# OBD_Board_Ver1.net
KiCad netlist of a schematic drawn in EAGLE
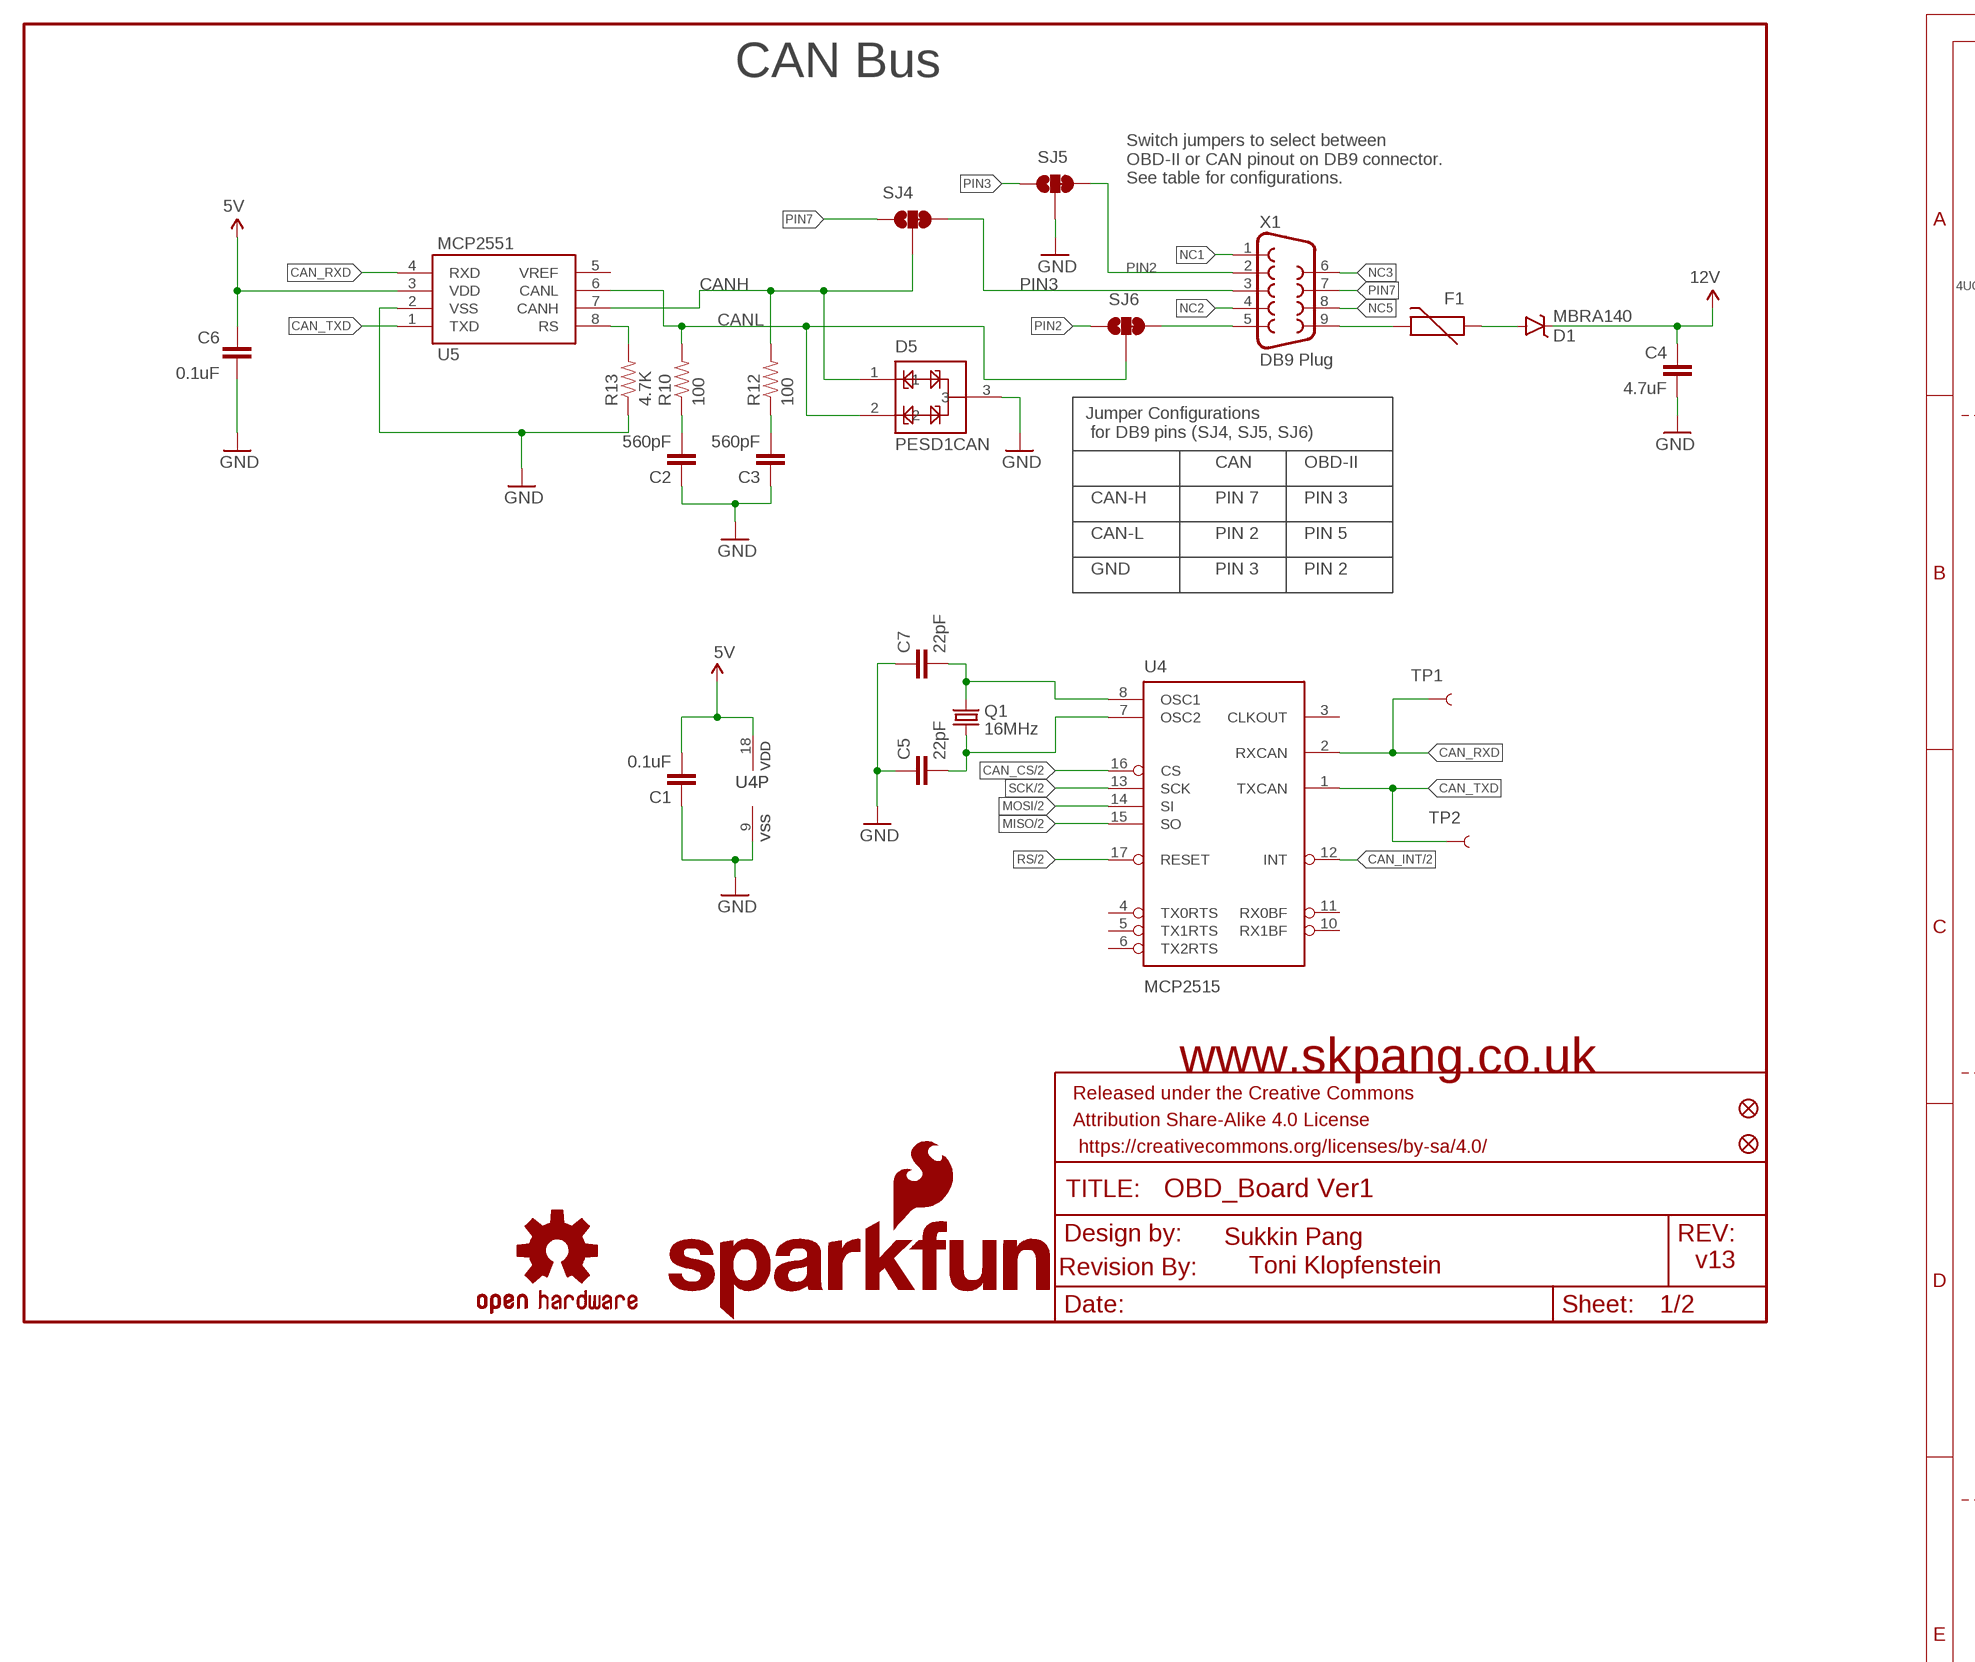
[diagram p0: schematic, sheet 1, part 1 of 2]
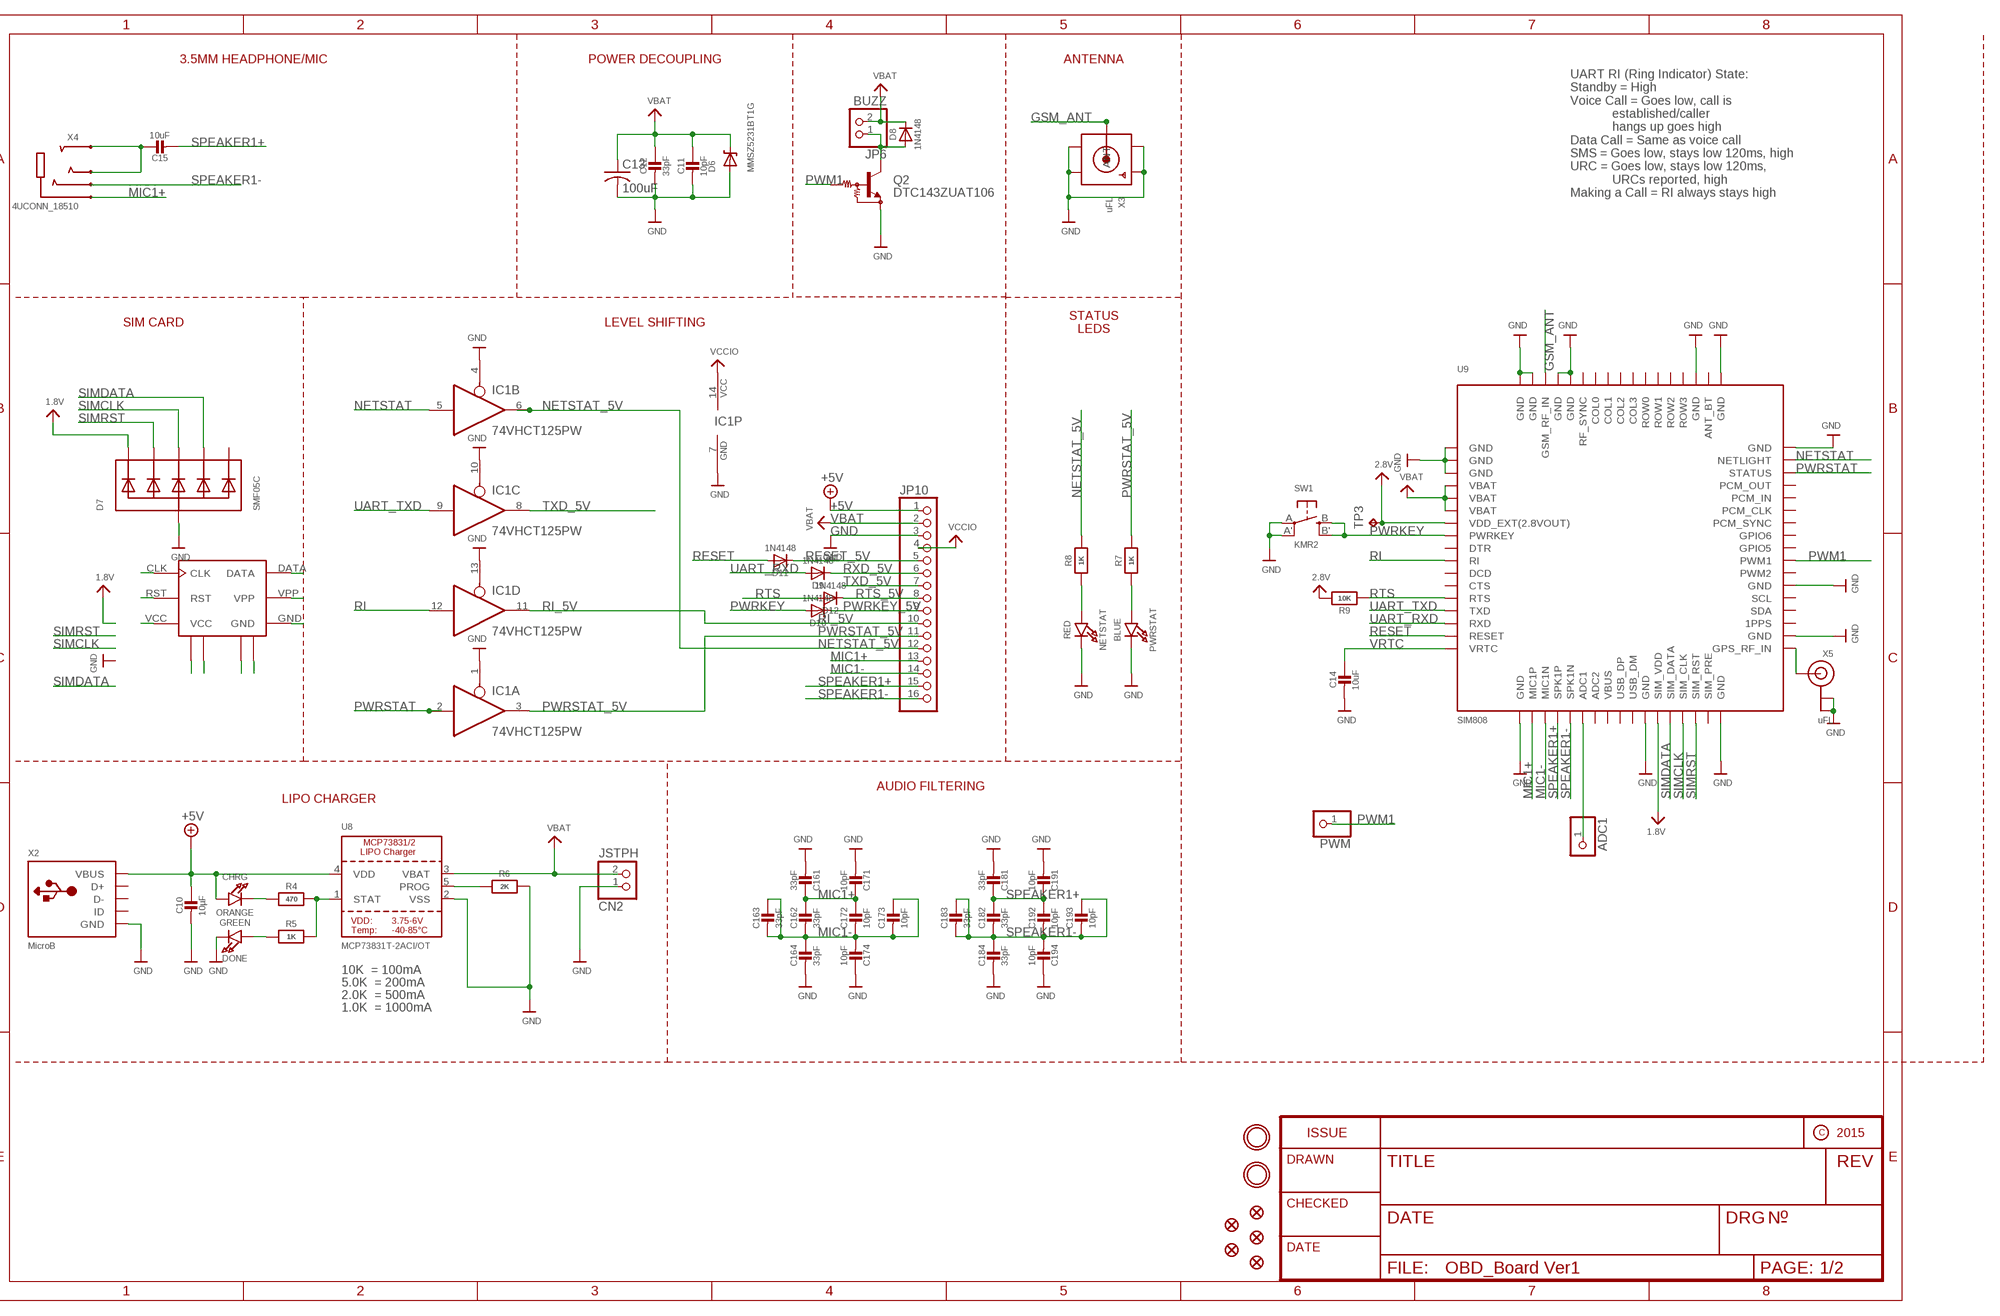
[diagram p1: schematic, sheet 1, part 2 of 2]
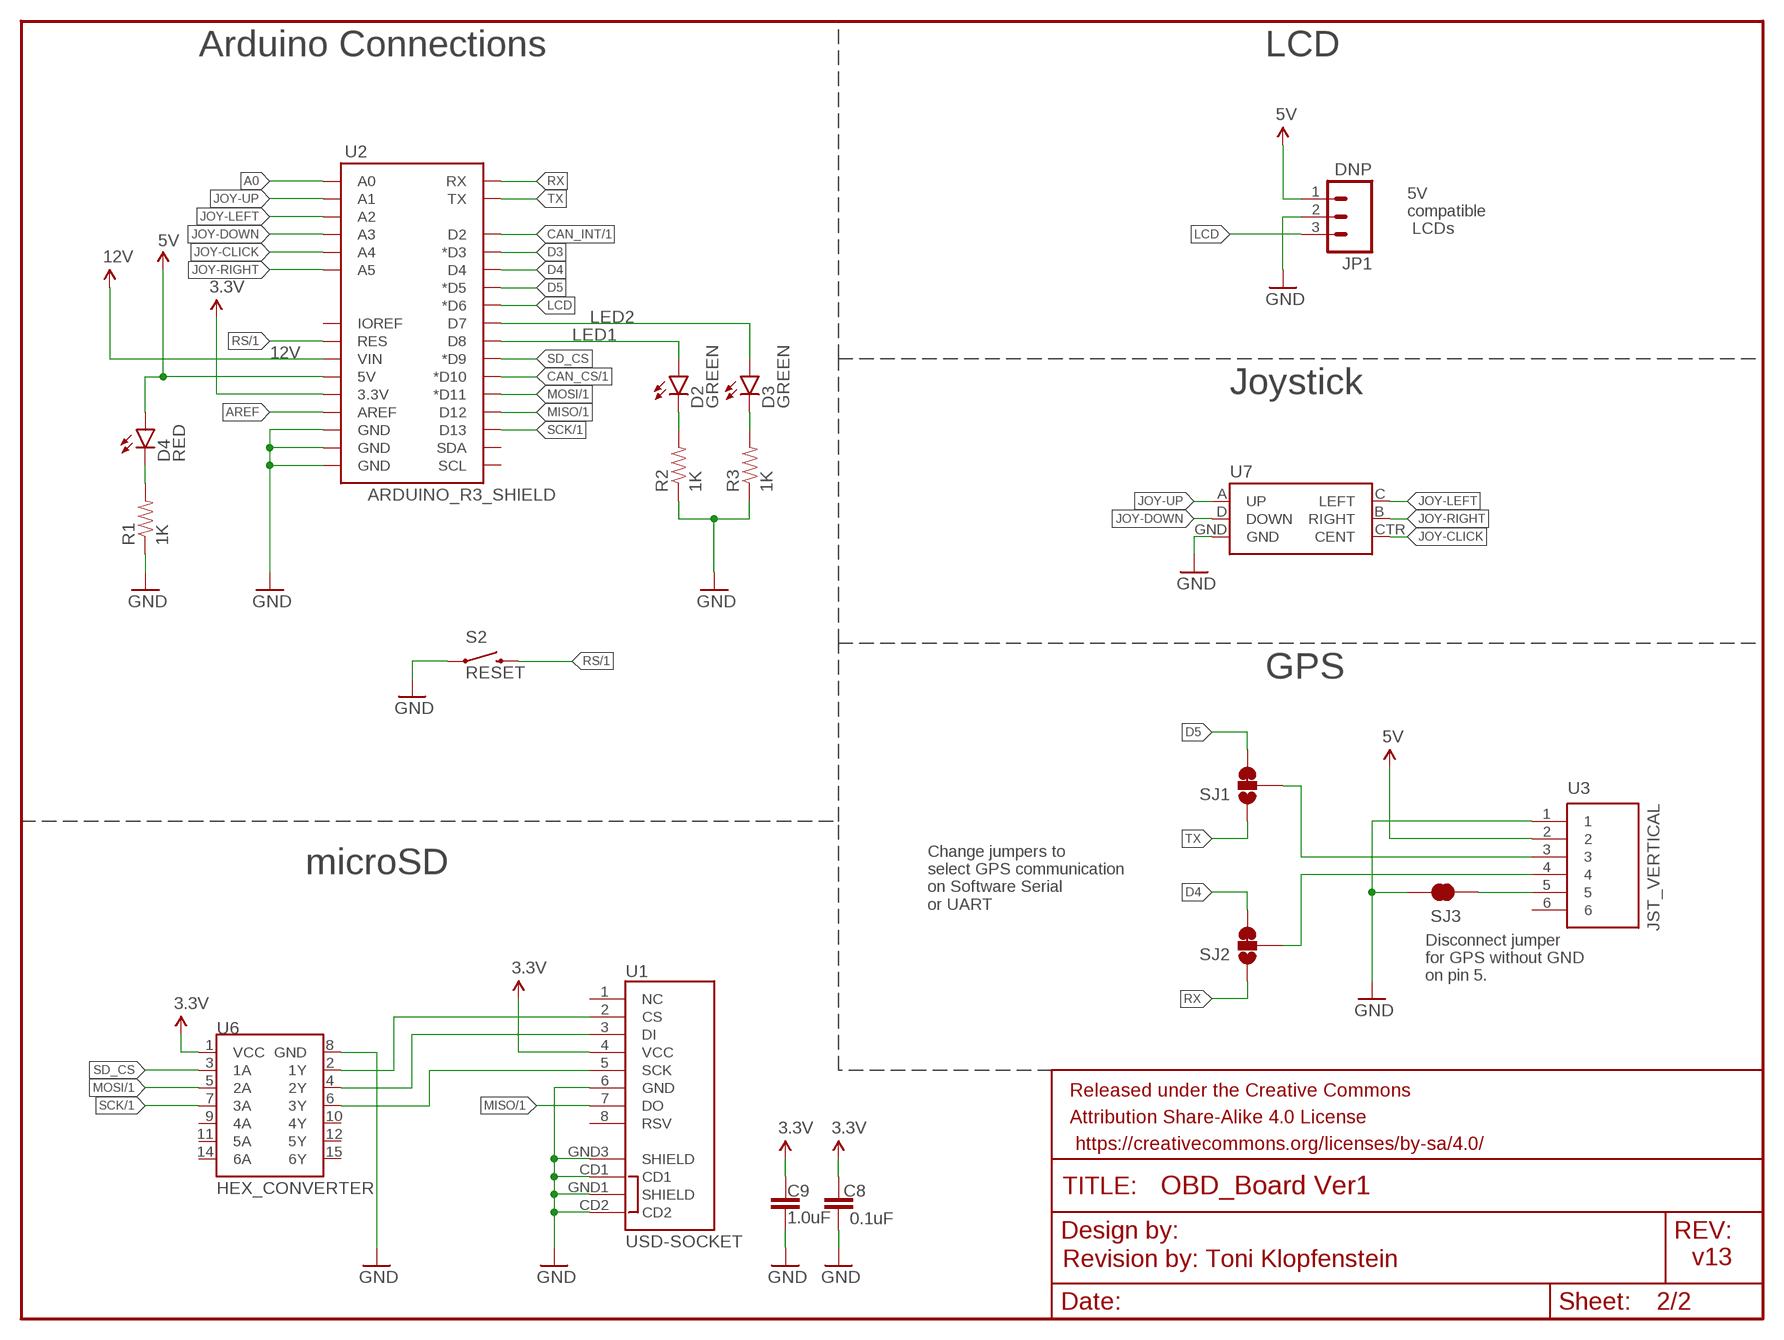
[diagram p2: schematic, sheet 2]

(export (version "E")
  (design (tool "Eeschema 10.0.6"))
  (components
    (comp (ref "C8")
      (value "0.1uF")
      (footprint "eagle-import:0603-CAP")
      (libsource (lib "eagle-import") (part "0.1UF-25V(+80/-20%)(0603)"))
    )
    (comp (ref "C9")
      (value "1.0uF")
      (footprint "eagle-import:0603-CAP")
      (libsource (lib "eagle-import") (part "1.0UF-16V-10%(0603)"))
    )
    (comp (ref "D2")
      (value "GREEN")
      (footprint "eagle-import:LED-0603")
      (libsource (lib "eagle-import") (part "LED-GREEN0603"))
    )
    (comp (ref "D3")
      (value "GREEN")
      (footprint "eagle-import:LED-0603")
      (libsource (lib "eagle-import") (part "LED-GREEN0603"))
    )
    (comp (ref "D4")
      (value "RED")
      (footprint "eagle-import:LED-0603")
      (libsource (lib "eagle-import") (part "LED-RED0603"))
    )
    (comp (ref "FRAME2")
      (value "FRAME-LETTERNO_PACKAGE")
      (footprint "eagle-import:DUMMY")
      (fields (field (name "DESIGNER") "Sukkin Pang and Ryan Owens") (field (name "VERSION") "v13"))
      (libsource (lib "eagle-import") (part "FRAME-LETTERNO_PACKAGE"))
    )
    (comp (ref "JP1")
      (value "DNP")
      (footprint "eagle-import:MOLEX-1X3_LOCK")
      (libsource (lib "eagle-import") (part "M03POLAR_LOCK"))
    )
    (comp (ref "R1")
      (value "1K")
      (footprint "eagle-import:0603-RES")
      (libsource (lib "eagle-import") (part "1KOHM-1/10W-1%(0603)"))
    )
    (comp (ref "R2")
      (value "1K")
      (footprint "eagle-import:0603-RES")
      (libsource (lib "eagle-import") (part "1KOHM-1/10W-1%(0603)"))
    )
    (comp (ref "R3")
      (value "1K")
      (footprint "eagle-import:0603-RES")
      (libsource (lib "eagle-import") (part "1KOHM-1/10W-1%(0603)"))
    )
    (comp (ref "S2")
      (value "RESET")
      (footprint "eagle-import:TACTILE-SWITCH-SMD")
      (libsource (lib "eagle-import") (part "SWITCH-MOMENTARY-2SMD"))
    )
    (comp (ref "SJ1")
      (value "JUMPER-PAD-3-2OF3_NC_BY_TRACE_SMALL")
      (footprint "eagle-import:PAD-JUMPER-3-2OF3_NC_BY_TRACE_YES_SILK_FULL_BOX")
      (libsource (lib "eagle-import") (part "JUMPER-PAD-3-2OF3_NC_BY_TRACE_SMALL"))
    )
    (comp (ref "SJ2")
      (value "JUMPER-PAD-3-2OF3_NC_BY_TRACE_SMALL")
      (footprint "eagle-import:PAD-JUMPER-3-2OF3_NC_BY_TRACE_YES_SILK_FULL_BOX")
      (libsource (lib "eagle-import") (part "JUMPER-PAD-3-2OF3_NC_BY_TRACE_SMALL"))
    )
    (comp (ref "SJ3")
      (value "JUMPER-PAD-2-NC_BY_TRACE")
      (footprint "eagle-import:PAD-JUMPER-2-NC_BY_TRACE_YES_SILK")
      (libsource (lib "eagle-import") (part "JUMPER-PAD-2-NC_BY_TRACE"))
    )
    (comp (ref "U1")
      (value "USD-SOCKET")
      (footprint "eagle-import:MICROSD_1_1")
      (libsource (lib "eagle-import") (part "USD-SOCKET"))
    )
    (comp (ref "U2")
      (value "ARDUINO_R3_SHIELD")
      (footprint "eagle-import:UNO_R3_SHIELD")
      (libsource (lib "eagle-import") (part "ARDUINO_R3_SHIELD"))
    )
    (comp (ref "U3")
      (value "JST_VERTICAL")
      (footprint "eagle-import:JST-6-SMD-VERT-1.0MM")
      (libsource (lib "eagle-import") (part "JST_VERTICAL"))
    )
    (comp (ref "U6")
      (value "HEX_CONVERTER")
      (footprint "eagle-import:SO016")
      (libsource (lib "eagle-import") (part "HEX_CONVERTER"))
    )
    (comp (ref "U7")
      (value "JOYSTICK_MINI")
      (footprint "eagle-import:JOYSTICK_MINI")
      (libsource (lib "eagle-import") (part "JOYSTICK_MINI"))
    )
    (comp (ref "ADC1")
      (value "PINHD-1X1CB")
      (footprint "eagle-import:1X01-CLEANBIG")
      (libsource (lib "eagle-import") (part "PINHD-1X1CB"))
    )
    (comp (ref "C1")
      (value "0.1uF")
      (footprint "eagle-import:0603-CAP")
      (libsource (lib "eagle-import") (part "0.1UF-25V(+80/-20%)(0603)"))
    )
    (comp (ref "C2")
      (value "560pF")
      (footprint "eagle-import:0603-CAP")
      (libsource (lib "eagle-import") (part "560PF-50V-5%(0603)"))
    )
    (comp (ref "C3")
      (value "560pF")
      (footprint "eagle-import:0603-CAP")
      (libsource (lib "eagle-import") (part "560PF-50V-5%(0603)"))
    )
    (comp (ref "C4")
      (value "4.7uF")
      (footprint "eagle-import:0603-CAP")
      (libsource (lib "eagle-import") (part "4.7UF-6.3V-10%(0603)0603"))
    )
    (comp (ref "C5")
      (value "22pF")
      (footprint "eagle-import:0603-CAP")
      (libsource (lib "eagle-import") (part "22PF-50V-5%(0603)"))
    )
    (comp (ref "C6")
      (value "0.1uF")
      (footprint "eagle-import:0603-CAP")
      (libsource (lib "eagle-import") (part "0.1UF-25V(+80/-20%)(0603)"))
    )
    (comp (ref "C7")
      (value "22pF")
      (footprint "eagle-import:0603-CAP")
      (libsource (lib "eagle-import") (part "22PF-50V-5%(0603)"))
    )
    (comp (ref "C10")
      (value "10µF")
      (footprint "eagle-import:0805-NO")
      (libsource (lib "eagle-import") (part "CAP_CERAMIC0805-NOOUTLINE"))
    )
    (comp (ref "C11")
      (value "10pF")
      (footprint "eagle-import:0805-NO")
      (libsource (lib "eagle-import") (part "CAP_CERAMIC0805-NOOUTLINE"))
    )
    (comp (ref "C12")
      (value "33pF")
      (footprint "eagle-import:0805-NO")
      (libsource (lib "eagle-import") (part "CAP_CERAMIC0805-NOOUTLINE"))
    )
    (comp (ref "C13")
      (value "100uF")
      (footprint "eagle-import:C1210")
      (libsource (lib "eagle-import") (part "C-USC1210"))
    )
    (comp (ref "C14")
      (value "10uF")
      (footprint "eagle-import:0805-NO")
      (libsource (lib "eagle-import") (part "CAP_CERAMIC0805-NOOUTLINE"))
    )
    (comp (ref "C15")
      (value "10uF")
      (footprint "eagle-import:0805-NO")
      (libsource (lib "eagle-import") (part "CAP_CERAMIC0805-NOOUTLINE"))
    )
    (comp (ref "C16")
      (value "33pF")
      (footprint "eagle-import:RESPACK_4X0603")
      (libsource (lib "eagle-import") (part "CAP_4PACK1206"))
    )
    (comp (ref "C17")
      (value "10pF")
      (footprint "eagle-import:RESPACK_4X0603")
      (libsource (lib "eagle-import") (part "CAP_4PACK1206"))
    )
    (comp (ref "C18")
      (value "33pF")
      (footprint "eagle-import:RESPACK_4X0603")
      (libsource (lib "eagle-import") (part "CAP_4PACK1206"))
    )
    (comp (ref "C19")
      (value "10pF")
      (footprint "eagle-import:RESPACK_4X0603")
      (libsource (lib "eagle-import") (part "CAP_4PACK1206"))
    )
    (comp (ref "CHRG")
      (value "ORANGE")
      (footprint "eagle-import:CHIPLED_0805_NOOUTLINE")
      (libsource (lib "eagle-import") (part "LED0805_NOOUTLINE"))
    )
    (comp (ref "CN2")
      (value "JSTPH")
      (footprint "eagle-import:JSTPH2")
      (libsource (lib "eagle-import") (part "JST_2PIN"))
    )
    (comp (ref "D1")
      (value "MBRA140")
      (footprint "eagle-import:SMA-DIODE")
      (libsource (lib "eagle-import") (part "MBRA140"))
    )
    (comp (ref "D5")
      (value "PESD1CAN")
      (footprint "eagle-import:SOT23-3")
      (libsource (lib "eagle-import") (part "PESD1CAN"))
    )
    (comp (ref "D6")
      (value "MMSZ5231BT1G")
      (footprint "eagle-import:SOD-123")
      (libsource (lib "eagle-import") (part "DIODE-ZENERSOD123"))
    )
    (comp (ref "D7")
      (value "SMF05C")
      (footprint "eagle-import:SOT363")
      (libsource (lib "eagle-import") (part "TVSARRAY_5LANE"))
    )
    (comp (ref "D8")
      (value "1N4148")
      (footprint "eagle-import:SOD-323")
      (libsource (lib "eagle-import") (part "DIODESOD-323"))
    )
    (comp (ref "D9")
      (value "1N4148")
      (footprint "eagle-import:SOD-323")
      (libsource (lib "eagle-import") (part "DIODESOD-323"))
    )
    (comp (ref "D10")
      (value "1N4148")
      (footprint "eagle-import:SOD-323")
      (libsource (lib "eagle-import") (part "DIODESOD-323"))
    )
    (comp (ref "D11")
      (value "1N4148")
      (footprint "eagle-import:SOD-323")
      (libsource (lib "eagle-import") (part "DIODESOD-323"))
    )
    (comp (ref "D12")
      (value "1N4148")
      (footprint "eagle-import:SOD-323")
      (libsource (lib "eagle-import") (part "DIODESOD-323"))
    )
    (comp (ref "DONE")
      (value "GREEN")
      (footprint "eagle-import:CHIPLED_0805_NOOUTLINE")
      (libsource (lib "eagle-import") (part "LED0805_NOOUTLINE"))
    )
    (comp (ref "F1")
      (value "PTCTHERMISTOR1206")
      (footprint "eagle-import:PTC-1206")
      (libsource (lib "eagle-import") (part "PTCTHERMISTOR1206"))
    )
    (comp (ref "FID1")
      (value "FIDUCIAL\"\"")
      (footprint "eagle-import:FIDUCIAL_1MM")
      (libsource (lib "eagle-import") (part "FIDUCIAL{dblquote}{dblquote}"))
    )
    (comp (ref "FID2")
      (value "FIDUCIAL\"\"")
      (footprint "eagle-import:FIDUCIAL_1MM")
      (libsource (lib "eagle-import") (part "FIDUCIAL{dblquote}{dblquote}"))
    )
    (comp (ref "FID3")
      (value "FIDUCIAL\"\"")
      (footprint "eagle-import:FIDUCIAL_1MM")
      (libsource (lib "eagle-import") (part "FIDUCIAL{dblquote}{dblquote}"))
    )
    (comp (ref "FID4")
      (value "FIDUCIAL\"\"")
      (footprint "eagle-import:FIDUCIAL_1MM")
      (libsource (lib "eagle-import") (part "FIDUCIAL{dblquote}{dblquote}"))
    )
    (comp (ref "FID5")
      (value "FIDUCIAL\"\"")
      (footprint "eagle-import:FIDUCIAL_1MM")
      (libsource (lib "eagle-import") (part "FIDUCIAL{dblquote}{dblquote}"))
    )
    (comp (ref "FRAME1")
      (value "FRAME-LETTER")
      (footprint "eagle-import:CREATIVE_COMMONS")
      (libsource (lib "eagle-import") (part "FRAME-LETTER"))
    )
    (comp (ref "IC1")
      (value "74VHCT125PW")
      (footprint "eagle-import:TSSOP14")
      (libsource (lib "eagle-import") (part "74125PWABT"))
    )
    (comp (ref "JP2")
      (value "FIDUCIAL1X2")
      (footprint "eagle-import:FIDUCIAL-1X2")
      (libsource (lib "eagle-import") (part "FIDUCIAL1X2"))
    )
    (comp (ref "JP3")
      (value "FIDUCIAL1X2")
      (footprint "eagle-import:FIDUCIAL-1X2")
      (libsource (lib "eagle-import") (part "FIDUCIAL1X2"))
    )
    (comp (ref "JP4")
      (value "SFE_LOGO_NAME_FLAME.1_INCH")
      (footprint "eagle-import:SFE_LOGO_NAME_FLAME_.1")
      (libsource (lib "eagle-import") (part "SFE_LOGO_NAME_FLAME.1_INCH"))
    )
    (comp (ref "JP6")
      (value "BUZZ")
      (footprint "eagle-import:1X02_ROUND")
      (libsource (lib "eagle-import") (part "HEADER-1X2ROUND"))
    )
    (comp (ref "JP10")
      (value "HEADER-1X16ROUND")
      (footprint "eagle-import:1X16_ROUND")
      (libsource (lib "eagle-import") (part "HEADER-1X16ROUND"))
    )
    (comp (ref "LOGO1")
      (value "OSHW-LOGOM")
      (footprint "eagle-import:OSHW-LOGO-M")
      (libsource (lib "eagle-import") (part "OSHW-LOGOM"))
    )
    (comp (ref "NETSTAT")
      (value "RED")
      (footprint "eagle-import:CHIPLED_0805_NOOUTLINE")
      (libsource (lib "eagle-import") (part "LED0805_NOOUTLINE"))
    )
    (comp (ref "PWM")
      (value "PINHD-1X1CB")
      (footprint "eagle-import:1X01-CLEANBIG")
      (libsource (lib "eagle-import") (part "PINHD-1X1CB"))
    )
    (comp (ref "PWRSTAT")
      (value "BLUE")
      (footprint "eagle-import:CHIPLED_0805_NOOUTLINE")
      (libsource (lib "eagle-import") (part "LED0805_NOOUTLINE"))
    )
    (comp (ref "Q1")
      (value "16MHz")
      (footprint "eagle-import:CRYSTAL-SMD-5X3")
      (libsource (lib "eagle-import") (part "CRYSTAL5X3"))
    )
    (comp (ref "Q2")
      (value "DTC143ZUAT106")
      (footprint "eagle-import:SC59-BEC")
      (libsource (lib "eagle-import") (part "-NPN_DRIVER-SC59-BECMUN2211T1"))
    )
    (comp (ref "R4")
      (value "470")
      (footprint "eagle-import:0805-NO")
      (libsource (lib "eagle-import") (part "RESISTOR0805_NOOUTLINE"))
    )
    (comp (ref "R5")
      (value "1K")
      (footprint "eagle-import:0805-NO")
      (libsource (lib "eagle-import") (part "RESISTOR0805_NOOUTLINE"))
    )
    (comp (ref "R6")
      (value "2K")
      (footprint "eagle-import:0805-NO")
      (libsource (lib "eagle-import") (part "RESISTOR0805_NOOUTLINE"))
    )
    (comp (ref "R7")
      (value "1K")
      (footprint "eagle-import:0805-NO")
      (libsource (lib "eagle-import") (part "RESISTOR0805_NOOUTLINE"))
    )
    (comp (ref "R8")
      (value "1K")
      (footprint "eagle-import:0805-NO")
      (libsource (lib "eagle-import") (part "RESISTOR0805_NOOUTLINE"))
    )
    (comp (ref "R9")
      (value "10K")
      (footprint "eagle-import:0805-NO")
      (libsource (lib "eagle-import") (part "RESISTOR0805_NOOUTLINE"))
    )
    (comp (ref "R10")
      (value "100")
      (footprint "eagle-import:0603-RES")
      (libsource (lib "eagle-import") (part "100OHM-1/10W-1%(0603)"))
    )
    (comp (ref "R12")
      (value "100")
      (footprint "eagle-import:0603-RES")
      (libsource (lib "eagle-import") (part "100OHM-1/10W-1%(0603)"))
    )
    (comp (ref "R13")
      (value "4.7K")
      (footprint "eagle-import:0603-RES")
      (libsource (lib "eagle-import") (part "4.7KOHM-1/10W-1%(0603)"))
    )
    (comp (ref "SJ4")
      (value "JUMPER-PAD-3-2OF3_NC_BY_TRACE_SMALL")
      (footprint "eagle-import:PAD-JUMPER-3-2OF3_NC_BY_TRACE_YES_SILK_FULL_BOX")
      (libsource (lib "eagle-import") (part "JUMPER-PAD-3-2OF3_NC_BY_TRACE_SMALL"))
    )
    (comp (ref "SJ5")
      (value "JUMPER-PAD-3-2OF3_NC_BY_TRACE_SMALL")
      (footprint "eagle-import:PAD-JUMPER-3-2OF3_NC_BY_TRACE_YES_SILK_FULL_BOX")
      (libsource (lib "eagle-import") (part "JUMPER-PAD-3-2OF3_NC_BY_TRACE_SMALL"))
    )
    (comp (ref "SJ6")
      (value "JUMPER-PAD-3-2OF3_NC_BY_TRACE_SMALL")
      (footprint "eagle-import:PAD-JUMPER-3-2OF3_NC_BY_TRACE_YES_SILK_FULL_BOX")
      (libsource (lib "eagle-import") (part "JUMPER-PAD-3-2OF3_NC_BY_TRACE_SMALL"))
    )
    (comp (ref "SW1")
      (value "KMR2")
      (footprint "eagle-import:BTN_KMR2_4.6X2.8")
      (libsource (lib "eagle-import") (part "SWITCH_TACT_SMT4.6X2.8"))
    )
    (comp (ref "TP1")
      (value "TEST-POINT3X5")
      (footprint "eagle-import:PAD.03X.05")
      (libsource (lib "eagle-import") (part "TEST-POINT3X5"))
    )
    (comp (ref "TP2")
      (value "TEST-POINT3X5")
      (footprint "eagle-import:PAD.03X.05")
      (libsource (lib "eagle-import") (part "TEST-POINT3X5"))
    )
    (comp (ref "TP3")
      (value "TPTP11R")
      (footprint "eagle-import:TP11R")
      (libsource (lib "eagle-import") (part "TPTP11R"))
    )
    (comp (ref "U$1")
      (value "REVISION")
      (footprint "eagle-import:REVISION")
      (libsource (lib "eagle-import") (part "REVISION"))
    )
    (comp (ref "U$25")
      (value "SCU-W0822XR-06")
      (footprint "eagle-import:SCU-W0822XR-06")
      (libsource (lib "eagle-import") (part "SCU-W0822XR-06"))
    )
    (comp (ref "U$33")
      (value "MOUNTINGHOLE2.5")
      (footprint "eagle-import:MOUNTINGHOLE_2.5_PLATED")
      (libsource (lib "eagle-import") (part "MOUNTINGHOLE2.5"))
    )
    (comp (ref "U$34")
      (value "MOUNTINGHOLE2.5")
      (footprint "eagle-import:MOUNTINGHOLE_2.5_PLATED")
      (libsource (lib "eagle-import") (part "MOUNTINGHOLE2.5"))
    )
    (comp (ref "U4")
      (value "MCP2515")
      (footprint "eagle-import:SO-18W")
      (libsource (lib "eagle-import") (part "MCP2510SO"))
    )
    (comp (ref "U5")
      (value "MCP2551")
      (footprint "eagle-import:SO08")
      (libsource (lib "eagle-import") (part "MCP2551"))
    )
    (comp (ref "U8")
      (value "MCP73831T-2ACI/OT")
      (footprint "eagle-import:SOT23-5")
      (libsource (lib "eagle-import") (part "MCP73831/2"))
    )
    (comp (ref "U9")
      (value "SIM808")
      (footprint "eagle-import:SIM900_SMT")
      (libsource (lib "eagle-import") (part "GSM_SIM808_LITERAL"))
    )
    (comp (ref "X1")
      (value "DB9 Plug")
      (footprint "eagle-import:DB9_MALE")
      (libsource (lib "eagle-import") (part "DB9MALE"))
    )
    (comp (ref "X2")
      (value "MicroB")
      (footprint "eagle-import:4UCONN_20329")
      (libsource (lib "eagle-import") (part "USBMICRO_20329"))
    )
    (comp (ref "X3")
      (value "uFL")
      (footprint "eagle-import:SMA_EDGELAUNCH_UFL")
      (libsource (lib "eagle-import") (part "SMACONNECTOR_EDGE_UFL"))
    )
    (comp (ref "X4")
      (value "4UCONN_18510")
      (footprint "eagle-import:4UCONN_18510")
      (libsource (lib "eagle-import") (part "AUDIO_3.5MMJACK_4POL"))
    )
    (comp (ref "X5")
      (value "uFL")
      (footprint "eagle-import:U.FL")
      (libsource (lib "eagle-import") (part "ANTENNA_U.FL"))
    )
  )
  (nets
    (net (code "1") (name "+5V") (class "Default")
      (node (ref "C10") (pin "1") (pinfunction "1_1") (pintype "passive"))
      (node (ref "CHRG") (pin "A") (pinfunction "A_A") (pintype "passive"))
      (node (ref "JP10") (pin "1") (pinfunction "1_1") (pintype "passive"))
      (node (ref "U8") (pin "4") (pinfunction "VDD_4") (pintype "power_in"))
      (node (ref "X2") (pin "VBUS") (pinfunction "VBUS_VBUS") (pintype "power_in"))
    )
    (net (code "2") (name "1.8V") (class "Default")
      (node (ref "D7") (pin "1") (pinfunction "C1_1") (pintype "passive"))
      (node (ref "U$25") (pin "VCC") (pinfunction "VCC_VCC") (pintype "power_in"))
      (node (ref "U9") (pin "P$29") (pinfunction "SIM_VDD_P$29") (pintype "power_in"))
    )
    (net (code "3") (name "2.8V") (class "Default")
      (node (ref "R9") (pin "2") (pinfunction "2_2") (pintype "passive"))
      (node (ref "TP3") (pin "TP") (pinfunction "TP_TP") (pintype "input"))
      (node (ref "U9") (pin "P$7") (pinfunction "VDD_EXT(2.8VOUT)_P$7") (pintype "power_in"))
    )
    (net (code "4") (name "3.3V") (class "Default")
      (node (ref "C8") (pin "2") (pinfunction "2_2") (pintype "passive"))
      (node (ref "C9") (pin "1") (pinfunction "1_1") (pintype "passive"))
      (node (ref "U1") (pin "4") (pinfunction "VCC_4") (pintype "bidirectional"))
      (node (ref "U2") (pin "3.3V") (pinfunction "3.3V_3.3V") (pintype "bidirectional"))
      (node (ref "U6") (pin "1") (pinfunction "VCC_1") (pintype "bidirectional"))
    )
    (net (code "5") (name "5V") (class "Default")
      (node (ref "C1") (pin "2") (pinfunction "2_2") (pintype "passive"))
      (node (ref "C6") (pin "2") (pinfunction "2_2") (pintype "passive"))
      (node (ref "D4") (pin "A") (pinfunction "A_A") (pintype "passive"))
      (node (ref "JP1") (pin "1") (pinfunction "1_1") (pintype "passive"))
      (node (ref "U2") (pin "5V") (pinfunction "5V_5V") (pintype "bidirectional"))
      (node (ref "U3") (pin "2") (pinfunction "2_2") (pintype "bidirectional"))
      (node (ref "U4") (pin "18") (pinfunction "VDD_18") (pintype "power_in"))
      (node (ref "U5") (pin "3") (pinfunction "VDD_3") (pintype "bidirectional"))
    )
    (net (code "6") (name "12V") (class "Default")
      (node (ref "C4") (pin "1") (pinfunction "1_1") (pintype "passive"))
      (node (ref "D1") (pin "C") (pinfunction "C_C") (pintype "passive"))
      (node (ref "U2") (pin "VIN") (pinfunction "VIN_VIN") (pintype "bidirectional"))
    )
    (net (code "7") (name "A0") (class "Default")
      (node (ref "U2") (pin "A0") (pinfunction "A0_A0") (pintype "bidirectional"))
    )
    (net (code "8") (name "AREF") (class "Default")
      (node (ref "U2") (pin "AREF") (pinfunction "AREF_AREF") (pintype "bidirectional"))
    )
    (net (code "9") (name "CANH") (class "Default")
      (node (ref "D5") (pin "1") (pinfunction "1_1") (pintype "bidirectional"))
      (node (ref "R12") (pin "2") (pinfunction "2_2") (pintype "passive"))
      (node (ref "SJ4") (pin "2") (pinfunction "2_2") (pintype "passive"))
      (node (ref "U5") (pin "7") (pinfunction "CANH_7") (pintype "bidirectional"))
    )
    (net (code "10") (name "CANL") (class "Default")
      (node (ref "D5") (pin "2") (pinfunction "2_2") (pintype "bidirectional"))
      (node (ref "R10") (pin "2") (pinfunction "2_2") (pintype "passive"))
      (node (ref "SJ6") (pin "2") (pinfunction "2_2") (pintype "passive"))
      (node (ref "U5") (pin "6") (pinfunction "CANL_6") (pintype "bidirectional"))
    )
    (net (code "11") (name "CAN_CS") (class "Default")
      (node (ref "U2") (pin "D10") (pinfunction "*D10_D10") (pintype "bidirectional"))
      (node (ref "U4") (pin "16") (pinfunction "CS_16") (pintype "input"))
    )
    (net (code "12") (name "CAN_INT") (class "Default")
      (node (ref "U2") (pin "D2") (pinfunction "D2_D2") (pintype "bidirectional"))
      (node (ref "U4") (pin "12") (pinfunction "INT_12") (pintype "output"))
    )
    (net (code "13") (name "CAN_RXD") (class "Default")
      (node (ref "TP1") (pin "P$1") (pinfunction "1_P$1") (pintype "bidirectional"))
      (node (ref "U4") (pin "2") (pinfunction "RXCAN_2") (pintype "input"))
      (node (ref "U5") (pin "4") (pinfunction "RXD_4") (pintype "bidirectional"))
    )
    (net (code "14") (name "CAN_TXD") (class "Default")
      (node (ref "TP2") (pin "P$1") (pinfunction "1_P$1") (pintype "bidirectional"))
      (node (ref "U4") (pin "1") (pinfunction "TXCAN_1") (pintype "output"))
      (node (ref "U5") (pin "1") (pinfunction "TXD_1") (pintype "bidirectional"))
    )
    (net (code "15") (name "D3") (class "Default")
      (node (ref "U2") (pin "D3") (pinfunction "*D3_D3") (pintype "bidirectional"))
    )
    (net (code "16") (name "D4") (class "Default")
      (node (ref "SJ2") (pin "3") (pinfunction "3_3") (pintype "passive"))
      (node (ref "U2") (pin "D4") (pinfunction "D4_D4") (pintype "bidirectional"))
    )
    (net (code "17") (name "D5") (class "Default")
      (node (ref "SJ1") (pin "3") (pinfunction "3_3") (pintype "passive"))
      (node (ref "U2") (pin "D5") (pinfunction "*D5_D5") (pintype "bidirectional"))
    )
    (net (code "18") (name "GND") (class "Default")
      (node (ref "C1") (pin "1") (pinfunction "1_1") (pintype "passive"))
      (node (ref "C10") (pin "2") (pinfunction "2_2") (pintype "passive"))
      (node (ref "C11") (pin "2") (pinfunction "2_2") (pintype "passive"))
      (node (ref "C12") (pin "2") (pinfunction "2_2") (pintype "passive"))
      (node (ref "C13") (pin "2") (pinfunction "2_2") (pintype "passive"))
      (node (ref "C14") (pin "2") (pinfunction "2_2") (pintype "passive"))
      (node (ref "C16") (pin "5") (pinfunction "2_5") (pintype "passive"))
      (node (ref "C16") (pin "8") (pinfunction "2_8") (pintype "passive"))
      (node (ref "C17") (pin "4") (pinfunction "1_4") (pintype "passive"))
      (node (ref "C17") (pin "8") (pinfunction "2_8") (pintype "passive"))
      (node (ref "C18") (pin "5") (pinfunction "2_5") (pintype "passive"))
      (node (ref "C18") (pin "8") (pinfunction "2_8") (pintype "passive"))
      (node (ref "C19") (pin "4") (pinfunction "1_4") (pintype "passive"))
      (node (ref "C19") (pin "8") (pinfunction "2_8") (pintype "passive"))
      (node (ref "C2") (pin "1") (pinfunction "1_1") (pintype "passive"))
      (node (ref "C3") (pin "1") (pinfunction "1_1") (pintype "passive"))
      (node (ref "C4") (pin "2") (pinfunction "2_2") (pintype "passive"))
      (node (ref "C5") (pin "1") (pinfunction "1_1") (pintype "passive"))
      (node (ref "C6") (pin "1") (pinfunction "1_1") (pintype "passive"))
      (node (ref "C7") (pin "1") (pinfunction "1_1") (pintype "passive"))
      (node (ref "C8") (pin "1") (pinfunction "1_1") (pintype "passive"))
      (node (ref "C9") (pin "2") (pinfunction "2_2") (pintype "passive"))
      (node (ref "CN2") (pin "1") (pinfunction "1_1") (pintype "passive"))
      (node (ref "D5") (pin "3") (pinfunction "3_3") (pintype "bidirectional"))
      (node (ref "D6") (pin "A") (pinfunction "A_A") (pintype "passive"))
      (node (ref "D7") (pin "2") (pinfunction "A_2") (pintype "passive"))
      (node (ref "DONE") (pin "C") (pinfunction "C_C") (pintype "passive"))
      (node (ref "IC1") (pin "1") (pinfunction "OE_1") (pintype "input"))
      (node (ref "IC1") (pin "10") (pinfunction "OE_10") (pintype "input"))
      (node (ref "IC1") (pin "13") (pinfunction "OE_13") (pintype "input"))
      (node (ref "IC1") (pin "4") (pinfunction "OE_4") (pintype "input"))
      (node (ref "IC1") (pin "7") (pinfunction "GND_7") (pintype "power_in"))
      (node (ref "JP1") (pin "2") (pinfunction "2_2") (pintype "passive"))
      (node (ref "JP10") (pin "3") (pinfunction "3_3") (pintype "passive"))
      (node (ref "NETSTAT") (pin "C") (pinfunction "C_C") (pintype "passive"))
      (node (ref "PWRSTAT") (pin "C") (pinfunction "C_C") (pintype "passive"))
      (node (ref "Q2") (pin "E") (pinfunction "E_E") (pintype "passive"))
      (node (ref "R1") (pin "1") (pinfunction "1_1") (pintype "passive"))
      (node (ref "R13") (pin "1") (pinfunction "1_1") (pintype "passive"))
      (node (ref "R2") (pin "1") (pinfunction "1_1") (pintype "passive"))
      (node (ref "R3") (pin "1") (pinfunction "1_1") (pintype "passive"))
      (node (ref "R6") (pin "2") (pinfunction "2_2") (pintype "passive"))
      (node (ref "S2") (pin "1") (pinfunction "1_1") (pintype "passive"))
      (node (ref "SJ3") (pin "2") (pinfunction "2_2") (pintype "passive"))
      (node (ref "SJ5") (pin "2") (pinfunction "2_2") (pintype "passive"))
      (node (ref "SW1") (pin "A") (pinfunction "P_A") (pintype "passive"))
      (node (ref "SW1") (pin "A'") (pinfunction "P1_A'") (pintype "passive"))
      (node (ref "U$25") (pin "GND") (pinfunction "GND_GND") (pintype "power_in"))
      (node (ref "U$25") (pin "GND_1") (pinfunction "GND1_GND_1") (pintype "power_in"))
      (node (ref "U$25") (pin "GND_2") (pinfunction "GND2_GND_2") (pintype "power_in"))
      (node (ref "U$25") (pin "GND_3") (pinfunction "GND3_GND_3") (pintype "power_in"))
      (node (ref "U$25") (pin "GND_4") (pinfunction "GND4_GND_4") (pintype "power_in"))
      (node (ref "U1") (pin "6") (pinfunction "GND_6") (pintype "bidirectional"))
      (node (ref "U1") (pin "CD1") (pinfunction "CD1_CD1") (pintype "bidirectional"))
      (node (ref "U1") (pin "CD2") (pinfunction "CD2_CD2") (pintype "bidirectional"))
      (node (ref "U1") (pin "GND1") (pinfunction "SHIELD_GND1") (pintype "bidirectional"))
      (node (ref "U1") (pin "GND3") (pinfunction "SHIELD_GND3") (pintype "bidirectional"))
      (node (ref "U2") (pin "GND@0") (pinfunction "GND_GND@0") (pintype "bidirectional"))
      (node (ref "U2") (pin "GND@1") (pinfunction "GND_GND@1") (pintype "bidirectional"))
      (node (ref "U2") (pin "GND@2") (pinfunction "GND_GND@2") (pintype "bidirectional"))
      (node (ref "U3") (pin "1") (pinfunction "1_1") (pintype "bidirectional"))
      (node (ref "U4") (pin "9") (pinfunction "VSS_9") (pintype "power_in"))
      (node (ref "U5") (pin "2") (pinfunction "VSS_2") (pintype "bidirectional"))
      (node (ref "U6") (pin "8") (pinfunction "GND_8") (pintype "bidirectional"))
      (node (ref "U7") (pin "GND") (pinfunction "GND_GND") (pintype "bidirectional"))
      (node (ref "U8") (pin "2") (pinfunction "VSS_2") (pintype "power_in"))
      (node (ref "U9") (pin "P$1") (pinfunction "GND_P$1") (pintype "power_in"))
      (node (ref "U9") (pin "P$18") (pinfunction "GND_P$18") (pintype "power_in"))
      (node (ref "U9") (pin "P$2") (pinfunction "GND_P$2") (pintype "power_in"))
      (node (ref "U9") (pin "P$28") (pinfunction "GND_P$28") (pintype "power_in"))
      (node (ref "U9") (pin "P$3") (pinfunction "GND_P$3") (pintype "power_in"))
      (node (ref "U9") (pin "P$34") (pinfunction "GND_P$34") (pintype "power_in"))
      (node (ref "U9") (pin "P$36") (pinfunction "GND_P$36") (pintype "power_in"))
      (node (ref "U9") (pin "P$40") (pinfunction "GND_P$40") (pintype "power_in"))
      (node (ref "U9") (pin "P$51") (pinfunction "GND_P$51") (pintype "power_in"))
      (node (ref "U9") (pin "P$52") (pinfunction "GND_P$52") (pintype "power_in"))
      (node (ref "U9") (pin "P$54") (pinfunction "GND_P$54") (pintype "power_in"))
      (node (ref "U9") (pin "P$64") (pinfunction "GND_P$64") (pintype "power_in"))
      (node (ref "U9") (pin "P$65") (pinfunction "GND_P$65") (pintype "power_in"))
      (node (ref "U9") (pin "P$67") (pinfunction "GND_P$67") (pintype "power_in"))
      (node (ref "U9") (pin "P$68") (pinfunction "GND_P$68") (pintype "power_in"))
      (node (ref "X2") (pin "BASE@1") (pinfunction "GND_BASE@1") (pintype "power_in"))
      (node (ref "X2") (pin "BASE@2") (pinfunction "GND_BASE@2") (pintype "power_in"))
      (node (ref "X2") (pin "GND") (pinfunction "GND_GND") (pintype "power_in"))
      (node (ref "X2") (pin "SPRT@1") (pinfunction "GND_SPRT@1") (pintype "power_in"))
      (node (ref "X2") (pin "SPRT@2") (pinfunction "GND_SPRT@2") (pintype "power_in"))
      (node (ref "X2") (pin "SPRT@3") (pinfunction "GND_SPRT@3") (pintype "power_in"))
      (node (ref "X2") (pin "SPRT@4") (pinfunction "GND_SPRT@4") (pintype "power_in"))
      (node (ref "X3") (pin "GND@1") (pinfunction "GND1_GND@1") (pintype "power_in"))
      (node (ref "X3") (pin "GND@2") (pinfunction "GND2_GND@2") (pintype "power_in"))
      (node (ref "X3") (pin "GND@3") (pinfunction "GND3_GND@3") (pintype "power_in"))
      (node (ref "X3") (pin "GND@4") (pinfunction "GND4_GND@4") (pintype "power_in"))
      (node (ref "X5") (pin "1") (pinfunction "GND_1") (pintype "passive"))
      (node (ref "X5") (pin "2") (pinfunction "GND_2") (pintype "passive"))
    )
    (net (code "19") (name "GSM_ANT") (class "Default")
      (node (ref "U9") (pin "P$66") (pinfunction "GSM_RF_IN_P$66") (pintype "input"))
      (node (ref "X3") (pin "P") (pinfunction "ANT_P") (pintype "bidirectional"))
    )
    (net (code "20") (name "JOY-CLICK") (class "Default")
      (node (ref "U2") (pin "A4") (pinfunction "A4_A4") (pintype "bidirectional"))
      (node (ref "U7") (pin "CTR") (pinfunction "CENT_CTR") (pintype "bidirectional"))
    )
    (net (code "21") (name "JOY-DOWN") (class "Default")
      (node (ref "U2") (pin "A3") (pinfunction "A3_A3") (pintype "bidirectional"))
      (node (ref "U7") (pin "D") (pinfunction "DOWN_D") (pintype "bidirectional"))
    )
    (net (code "22") (name "JOY-LEFT") (class "Default")
      (node (ref "U2") (pin "A2") (pinfunction "A2_A2") (pintype "bidirectional"))
      (node (ref "U7") (pin "C") (pinfunction "LEFT_C") (pintype "bidirectional"))
    )
    (net (code "23") (name "JOY-RIGHT") (class "Default")
      (node (ref "U2") (pin "A5") (pinfunction "A5_A5") (pintype "bidirectional"))
      (node (ref "U7") (pin "B") (pinfunction "RIGHT_B") (pintype "bidirectional"))
    )
    (net (code "24") (name "JOY-UP") (class "Default")
      (node (ref "U2") (pin "A1") (pinfunction "A1_A1") (pintype "bidirectional"))
      (node (ref "U7") (pin "A") (pinfunction "UP_A") (pintype "bidirectional"))
    )
    (net (code "25") (name "LCD") (class "Default")
      (node (ref "JP1") (pin "3") (pinfunction "3_3") (pintype "passive"))
      (node (ref "U2") (pin "D6") (pinfunction "*D6_D6") (pintype "bidirectional"))
    )
    (net (code "26") (name "LED1") (class "Default")
      (node (ref "D2") (pin "A") (pinfunction "A_A") (pintype "passive"))
      (node (ref "U2") (pin "D8") (pinfunction "D8_D8") (pintype "bidirectional"))
    )
    (net (code "27") (name "LED2") (class "Default")
      (node (ref "D3") (pin "A") (pinfunction "A_A") (pintype "passive"))
      (node (ref "U2") (pin "D7") (pinfunction "D7_D7") (pintype "bidirectional"))
    )
    (net (code "28") (name "MIC1+") (class "Default")
      (node (ref "C16") (pin "1") (pinfunction "1_1") (pintype "passive"))
      (node (ref "C16") (pin "2") (pinfunction "1_2") (pintype "passive"))
      (node (ref "C17") (pin "1") (pinfunction "1_1") (pintype "passive"))
      (node (ref "C17") (pin "2") (pinfunction "1_2") (pintype "passive"))
      (node (ref "JP10") (pin "13") (pinfunction "13_13") (pintype "passive"))
      (node (ref "U9") (pin "P$19") (pinfunction "MIC1P_P$19") (pintype "input"))
      (node (ref "X4") (pin "1-GND") (pinfunction "TIP_1-GND") (pintype "passive"))
    )
    (net (code "29") (name "MIC1-") (class "Default")
      (node (ref "C16") (pin "3") (pinfunction "1_3") (pintype "passive"))
      (node (ref "C16") (pin "4") (pinfunction "1_4") (pintype "passive"))
      (node (ref "C16") (pin "6") (pinfunction "2_6") (pintype "passive"))
      (node (ref "C16") (pin "7") (pinfunction "2_7") (pintype "passive"))
      (node (ref "C17") (pin "3") (pinfunction "1_3") (pintype "passive"))
      (node (ref "C17") (pin "5") (pinfunction "2_5") (pintype "passive"))
      (node (ref "C17") (pin "6") (pinfunction "2_6") (pintype "passive"))
      (node (ref "C17") (pin "7") (pinfunction "2_7") (pintype "passive"))
      (node (ref "JP10") (pin "14") (pinfunction "14_14") (pintype "passive"))
      (node (ref "U9") (pin "P$20") (pinfunction "MIC1N_P$20") (pintype "input"))
    )
    (net (code "30") (name "MISO") (class "Default")
      (node (ref "U1") (pin "7") (pinfunction "DO_7") (pintype "bidirectional"))
      (node (ref "U2") (pin "D12") (pinfunction "D12_D12") (pintype "bidirectional"))
      (node (ref "U4") (pin "15") (pinfunction "SO_15") (pintype "output"))
    )
    (net (code "31") (name "MOSI") (class "Default")
      (node (ref "U2") (pin "D11") (pinfunction "*D11_D11") (pintype "bidirectional"))
      (node (ref "U4") (pin "14") (pinfunction "SI_14") (pintype "input"))
      (node (ref "U6") (pin "5") (pinfunction "2A_5") (pintype "bidirectional"))
    )
    (net (code "32") (name "NC1") (class "Default")
      (node (ref "X1") (pin "1") (pinfunction "1_1") (pintype "passive"))
    )
    (net (code "33") (name "NC2") (class "Default")
      (node (ref "X1") (pin "4") (pinfunction "4_4") (pintype "passive"))
    )
    (net (code "34") (name "NC3") (class "Default")
      (node (ref "X1") (pin "6") (pinfunction "6_6") (pintype "passive"))
    )
    (net (code "35") (name "NC5") (class "Default")
      (node (ref "X1") (pin "8") (pinfunction "8_8") (pintype "passive"))
    )
    (net (code "36") (name "NETSTAT") (class "Default")
      (node (ref "IC1") (pin "5") (pinfunction "I_5") (pintype "input"))
      (node (ref "U9") (pin "P$50") (pinfunction "NETLIGHT_P$50") (pintype "output"))
    )
    (net (code "37") (name "NETSTAT_5V") (class "Default")
      (node (ref "IC1") (pin "6") (pinfunction "O_6") (pintype "tri_state"))
      (node (ref "JP10") (pin "12") (pinfunction "12_12") (pintype "passive"))
      (node (ref "R8") (pin "2") (pinfunction "2_2") (pintype "passive"))
    )
    (net (code "38") (name "Net-(C2-Pad2)") (class "Default")
      (node (ref "C2") (pin "2") (pinfunction "2_2") (pintype "passive"))
      (node (ref "R10") (pin "1") (pinfunction "1_1") (pintype "passive"))
    )
    (net (code "39") (name "Net-(C3-Pad2)") (class "Default")
      (node (ref "C3") (pin "2") (pinfunction "2_2") (pintype "passive"))
      (node (ref "R12") (pin "1") (pinfunction "1_1") (pintype "passive"))
    )
    (net (code "40") (name "Net-(CHRG-PadC)") (class "Default")
      (node (ref "CHRG") (pin "C") (pinfunction "C_C") (pintype "passive"))
      (node (ref "R4") (pin "1") (pinfunction "1_1") (pintype "passive"))
    )
    (net (code "41") (name "Net-(D1-PadA)") (class "Default")
      (node (ref "D1") (pin "A") (pinfunction "A_A") (pintype "passive"))
      (node (ref "F1") (pin "1") (pinfunction "1_1") (pintype "bidirectional"))
    )
    (net (code "42") (name "Net-(D2-PadC)") (class "Default")
      (node (ref "D2") (pin "C") (pinfunction "C_C") (pintype "passive"))
      (node (ref "R2") (pin "2") (pinfunction "2_2") (pintype "passive"))
    )
    (net (code "43") (name "Net-(D3-PadC)") (class "Default")
      (node (ref "D3") (pin "C") (pinfunction "C_C") (pintype "passive"))
      (node (ref "R3") (pin "2") (pinfunction "2_2") (pintype "passive"))
    )
    (net (code "44") (name "Net-(D4-PadC)") (class "Default")
      (node (ref "D4") (pin "C") (pinfunction "C_C") (pintype "passive"))
      (node (ref "R1") (pin "2") (pinfunction "2_2") (pintype "passive"))
    )
    (net (code "45") (name "Net-(D8-PadA)") (class "Default")
      (node (ref "D8") (pin "A") (pinfunction "A_A") (pintype "passive"))
      (node (ref "JP6") (pin "1") (pinfunction "1_1") (pintype "passive"))
      (node (ref "Q2") (pin "C") (pinfunction "C_C") (pintype "passive"))
    )
    (net (code "46") (name "Net-(DONE-PadA)") (class "Default")
      (node (ref "DONE") (pin "A") (pinfunction "A_A") (pintype "passive"))
      (node (ref "R5") (pin "1") (pinfunction "1_1") (pintype "passive"))
    )
    (net (code "47") (name "Net-(F1-Pad2)") (class "Default")
      (node (ref "F1") (pin "2") (pinfunction "2_2") (pintype "bidirectional"))
      (node (ref "X1") (pin "9") (pinfunction "9_9") (pintype "passive"))
    )
    (net (code "48") (name "Net-(NETSTAT-PadA)") (class "Default")
      (node (ref "NETSTAT") (pin "A") (pinfunction "A_A") (pintype "passive"))
      (node (ref "R8") (pin "1") (pinfunction "1_1") (pintype "passive"))
    )
    (net (code "49") (name "Net-(PWRSTAT-PadA)") (class "Default")
      (node (ref "PWRSTAT") (pin "A") (pinfunction "A_A") (pintype "passive"))
      (node (ref "R7") (pin "1") (pinfunction "1_1") (pintype "passive"))
    )
    (net (code "50") (name "Net-(Q1-2)") (class "Default")
      (node (ref "C7") (pin "2") (pinfunction "2_2") (pintype "passive"))
      (node (ref "Q1") (pin "3") (pinfunction "2_3") (pintype "passive"))
      (node (ref "U4") (pin "8") (pinfunction "OSC1_8") (pintype "input"))
    )
    (net (code "51") (name "Net-(SJ1-Pad2)") (class "Default")
      (node (ref "SJ1") (pin "2") (pinfunction "2_2") (pintype "passive"))
      (node (ref "U3") (pin "3") (pinfunction "3_3") (pintype "bidirectional"))
    )
    (net (code "52") (name "Net-(SJ2-Pad2)") (class "Default")
      (node (ref "SJ2") (pin "2") (pinfunction "2_2") (pintype "passive"))
      (node (ref "U3") (pin "4") (pinfunction "4_4") (pintype "bidirectional"))
    )
    (net (code "53") (name "Net-(SJ3-Pad1)") (class "Default")
      (node (ref "SJ3") (pin "1") (pinfunction "1_1") (pintype "passive"))
      (node (ref "U3") (pin "5") (pinfunction "5_5") (pintype "bidirectional"))
    )
    (net (code "54") (name "Net-(SJ6-Pad3)") (class "Default")
      (node (ref "SJ6") (pin "3") (pinfunction "3_3") (pintype "passive"))
      (node (ref "X1") (pin "5") (pinfunction "5_5") (pintype "passive"))
    )
    (net (code "55") (name "Net-(U1-CS)") (class "Default")
      (node (ref "U1") (pin "2") (pinfunction "CS_2") (pintype "bidirectional"))
      (node (ref "U6") (pin "2") (pinfunction "1Y_2") (pintype "bidirectional"))
    )
    (net (code "56") (name "Net-(U1-DI)") (class "Default")
      (node (ref "U1") (pin "3") (pinfunction "DI_3") (pintype "bidirectional"))
      (node (ref "U6") (pin "4") (pinfunction "2Y_4") (pintype "bidirectional"))
    )
    (net (code "57") (name "Net-(U1-SCK)") (class "Default")
      (node (ref "U1") (pin "5") (pinfunction "SCK_5") (pintype "bidirectional"))
      (node (ref "U6") (pin "6") (pinfunction "3Y_6") (pintype "bidirectional"))
    )
    (net (code "58") (name "Net-(U4A-OSC2)") (class "Default")
      (node (ref "C5") (pin "2") (pinfunction "2_2") (pintype "passive"))
      (node (ref "Q1") (pin "1") (pinfunction "1_1") (pintype "passive"))
      (node (ref "U4") (pin "7") (pinfunction "OSC2_7") (pintype "output"))
    )
    (net (code "59") (name "Net-(U5-RS)") (class "Default")
      (node (ref "R13") (pin "2") (pinfunction "2_2") (pintype "passive"))
      (node (ref "U5") (pin "8") (pinfunction "RS_8") (pintype "bidirectional"))
    )
    (net (code "60") (name "Net-(U8-PROG)") (class "Default")
      (node (ref "R6") (pin "1") (pinfunction "1_1") (pintype "passive"))
      (node (ref "U8") (pin "5") (pinfunction "PROG_5") (pintype "input"))
    )
    (net (code "61") (name "Net-(U8-STAT)") (class "Default")
      (node (ref "R4") (pin "2") (pinfunction "2_2") (pintype "passive"))
      (node (ref "R5") (pin "2") (pinfunction "2_2") (pintype "passive"))
      (node (ref "U8") (pin "1") (pinfunction "STAT_1") (pintype "output"))
    )
    (net (code "62") (name "Net-(U9-ADC1)") (class "Default")
      (node (ref "ADC1") (pin "1") (pinfunction "1_1") (pintype "passive"))
      (node (ref "U9") (pin "P$23") (pinfunction "ADC1_P$23") (pintype "input"))
    )
    (net (code "63") (name "Net-(U9-GPS_RF_IN)") (class "Default")
      (node (ref "U9") (pin "P$35") (pinfunction "GPS_RF_IN_P$35") (pintype "bidirectional"))
      (node (ref "X5") (pin "3") (pinfunction "SIGNAL_3") (pintype "passive"))
    )
    (net (code "64") (name "Net-(X4-RING2)") (class "Default")
      (node (ref "C15") (pin "1") (pinfunction "1_1") (pintype "passive"))
      (node (ref "X4") (pin "2-TIP") (pinfunction "RING3_2-TIP") (pintype "passive"))
      (node (ref "X4") (pin "3-OUTER_SLEEVE") (pinfunction "RING2_3-OUTER_SLEEVE") (pintype "passive"))
    )
    (net (code "65") (name "PIN2") (class "Default")
      (node (ref "SJ5") (pin "3") (pinfunction "3_3") (pintype "passive"))
      (node (ref "SJ6") (pin "1") (pinfunction "1_1") (pintype "passive"))
      (node (ref "X1") (pin "2") (pinfunction "2_2") (pintype "passive"))
    )
    (net (code "66") (name "PIN3") (class "Default")
      (node (ref "SJ4") (pin "3") (pinfunction "3_3") (pintype "passive"))
      (node (ref "SJ5") (pin "1") (pinfunction "1_1") (pintype "passive"))
      (node (ref "X1") (pin "3") (pinfunction "3_3") (pintype "passive"))
    )
    (net (code "67") (name "PIN7") (class "Default")
      (node (ref "SJ4") (pin "1") (pinfunction "1_1") (pintype "passive"))
      (node (ref "X1") (pin "7") (pinfunction "7_7") (pintype "passive"))
    )
    (net (code "68") (name "PWM1") (class "Default")
      (node (ref "PWM") (pin "1") (pinfunction "1_1") (pintype "passive"))
      (node (ref "Q2") (pin "B") (pinfunction "B_B") (pintype "passive"))
      (node (ref "U9") (pin "P$42") (pinfunction "PWM1_P$42") (pintype "output"))
    )
    (net (code "69") (name "PWRKEY") (class "Default")
      (node (ref "D10") (pin "A") (pinfunction "A_A") (pintype "passive"))
      (node (ref "SW1") (pin "B") (pinfunction "S_B") (pintype "passive"))
      (node (ref "SW1") (pin "B'") (pinfunction "S1_B'") (pintype "passive"))
      (node (ref "U9") (pin "P$8") (pinfunction "PWRKEY_P$8") (pintype "input"))
    )
    (net (code "70") (name "PWRKEY_5V") (class "Default")
      (node (ref "D10") (pin "C") (pinfunction "C_C") (pintype "passive"))
      (node (ref "JP10") (pin "9") (pinfunction "9_9") (pintype "passive"))
    )
    (net (code "71") (name "PWRSTAT") (class "Default")
      (node (ref "IC1") (pin "2") (pinfunction "I_2") (pintype "input"))
      (node (ref "U9") (pin "P$49") (pinfunction "STATUS_P$49") (pintype "output"))
    )
    (net (code "72") (name "PWRSTAT_5V") (class "Default")
      (node (ref "IC1") (pin "3") (pinfunction "O_3") (pintype "tri_state"))
      (node (ref "JP10") (pin "11") (pinfunction "11_11") (pintype "passive"))
      (node (ref "R7") (pin "2") (pinfunction "2_2") (pintype "passive"))
    )
    (net (code "73") (name "RESET") (class "Default")
      (node (ref "D11") (pin "A") (pinfunction "A_A") (pintype "passive"))
      (node (ref "U9") (pin "P$16") (pinfunction "RESET_P$16") (pintype "input"))
    )
    (net (code "74") (name "RESET_5V") (class "Default")
      (node (ref "D11") (pin "C") (pinfunction "C_C") (pintype "passive"))
      (node (ref "JP10") (pin "5") (pinfunction "5_5") (pintype "passive"))
    )
    (net (code "75") (name "RI") (class "Default")
      (node (ref "IC1") (pin "12") (pinfunction "I_12") (pintype "input"))
      (node (ref "U9") (pin "P$10") (pinfunction "RI_P$10") (pintype "output"))
    )
    (net (code "76") (name "RI_5V") (class "Default")
      (node (ref "IC1") (pin "11") (pinfunction "O_11") (pintype "tri_state"))
      (node (ref "JP10") (pin "10") (pinfunction "10_10") (pintype "passive"))
    )
    (net (code "77") (name "RS") (class "Default")
      (node (ref "S2") (pin "3") (pinfunction "2_3") (pintype "passive"))
      (node (ref "U2") (pin "RES") (pinfunction "RES_RES") (pintype "bidirectional"))
      (node (ref "U4") (pin "17") (pinfunction "RESET_17") (pintype "input"))
    )
    (net (code "78") (name "RTS") (class "Default")
      (node (ref "D12") (pin "A") (pinfunction "A_A") (pintype "passive"))
      (node (ref "R9") (pin "1") (pinfunction "1_1") (pintype "passive"))
      (node (ref "U9") (pin "P$13") (pinfunction "RTS_P$13") (pintype "input"))
    )
    (net (code "79") (name "RTS_5V") (class "Default")
      (node (ref "D12") (pin "C") (pinfunction "C_C") (pintype "passive"))
      (node (ref "JP10") (pin "8") (pinfunction "8_8") (pintype "passive"))
    )
    (net (code "80") (name "RX") (class "Default")
      (node (ref "SJ2") (pin "1") (pinfunction "1_1") (pintype "passive"))
      (node (ref "U2") (pin "RX") (pinfunction "RX_RX") (pintype "bidirectional"))
    )
    (net (code "81") (name "RXD_5V") (class "Default")
      (node (ref "D9") (pin "C") (pinfunction "C_C") (pintype "passive"))
      (node (ref "JP10") (pin "6") (pinfunction "6_6") (pintype "passive"))
    )
    (net (code "82") (name "SCK") (class "Default")
      (node (ref "U2") (pin "D13") (pinfunction "D13_D13") (pintype "bidirectional"))
      (node (ref "U4") (pin "13") (pinfunction "SCK_13") (pintype "input"))
      (node (ref "U6") (pin "7") (pinfunction "3A_7") (pintype "bidirectional"))
    )
    (net (code "83") (name "SD_CS") (class "Default")
      (node (ref "U2") (pin "D9") (pinfunction "*D9_D9") (pintype "bidirectional"))
      (node (ref "U6") (pin "3") (pinfunction "1A_3") (pintype "bidirectional"))
    )
    (net (code "84") (name "SIMCLK") (class "Default")
      (node (ref "D7") (pin "4") (pinfunction "C3_4") (pintype "passive"))
      (node (ref "U$25") (pin "CLK") (pinfunction "CLK_CLK") (pintype "input"))
      (node (ref "U9") (pin "P$31") (pinfunction "SIM_CLK_P$31") (pintype "output"))
    )
    (net (code "85") (name "SIMDATA") (class "Default")
      (node (ref "D7") (pin "5") (pinfunction "C4_5") (pintype "passive"))
      (node (ref "U$25") (pin "DATA") (pinfunction "DATA_DATA") (pintype "bidirectional"))
      (node (ref "U9") (pin "P$30") (pinfunction "SIM_DATA_P$30") (pintype "bidirectional"))
    )
    (net (code "86") (name "SIMRST") (class "Default")
      (node (ref "D7") (pin "3") (pinfunction "C2_3") (pintype "passive"))
      (node (ref "U$25") (pin "RST") (pinfunction "RST_RST") (pintype "input"))
      (node (ref "U9") (pin "P$32") (pinfunction "SIM_RST_P$32") (pintype "output"))
    )
    (net (code "87") (name "SPEAKER1+") (class "Default")
      (node (ref "C15") (pin "2") (pinfunction "2_2") (pintype "passive"))
      (node (ref "C18") (pin "1") (pinfunction "1_1") (pintype "passive"))
      (node (ref "C18") (pin "2") (pinfunction "1_2") (pintype "passive"))
      (node (ref "C19") (pin "1") (pinfunction "1_1") (pintype "passive"))
      (node (ref "C19") (pin "2") (pinfunction "1_2") (pintype "passive"))
      (node (ref "JP10") (pin "15") (pinfunction "15_15") (pintype "passive"))
      (node (ref "U9") (pin "P$21") (pinfunction "SPK1P_P$21") (pintype "output"))
    )
    (net (code "88") (name "SPEAKER1-") (class "Default")
      (node (ref "C18") (pin "3") (pinfunction "1_3") (pintype "passive"))
      (node (ref "C18") (pin "4") (pinfunction "1_4") (pintype "passive"))
      (node (ref "C18") (pin "6") (pinfunction "2_6") (pintype "passive"))
      (node (ref "C18") (pin "7") (pinfunction "2_7") (pintype "passive"))
      (node (ref "C19") (pin "3") (pinfunction "1_3") (pintype "passive"))
      (node (ref "C19") (pin "5") (pinfunction "2_5") (pintype "passive"))
      (node (ref "C19") (pin "6") (pinfunction "2_6") (pintype "passive"))
      (node (ref "C19") (pin "7") (pinfunction "2_7") (pintype "passive"))
      (node (ref "JP10") (pin "16") (pinfunction "16_16") (pintype "passive"))
      (node (ref "U9") (pin "P$22") (pinfunction "SPK1N_P$22") (pintype "output"))
      (node (ref "X4") (pin "4-INNER_SLEEVE") (pinfunction "RING1_4-INNER_SLEEVE") (pintype "passive"))
    )
    (net (code "89") (name "TX") (class "Default")
      (node (ref "SJ1") (pin "1") (pinfunction "1_1") (pintype "passive"))
      (node (ref "U2") (pin "TX") (pinfunction "TX_TX") (pintype "bidirectional"))
    )
    (net (code "90") (name "TXD_5V") (class "Default")
      (node (ref "IC1") (pin "8") (pinfunction "O_8") (pintype "tri_state"))
      (node (ref "JP10") (pin "7") (pinfunction "7_7") (pintype "passive"))
    )
    (net (code "91") (name "UART_RXD") (class "Default")
      (node (ref "D9") (pin "A") (pinfunction "A_A") (pintype "passive"))
      (node (ref "U9") (pin "P$15") (pinfunction "RXD_P$15") (pintype "input"))
    )
    (net (code "92") (name "UART_TXD") (class "Default")
      (node (ref "IC1") (pin "9") (pinfunction "I_9") (pintype "input"))
      (node (ref "U9") (pin "P$14") (pinfunction "TXD_P$14") (pintype "output"))
    )
    (net (code "93") (name "VBAT") (class "Default")
      (node (ref "C11") (pin "1") (pinfunction "1_1") (pintype "passive"))
      (node (ref "C12") (pin "1") (pinfunction "1_1") (pintype "passive"))
      (node (ref "C13") (pin "1") (pinfunction "1_1") (pintype "passive"))
      (node (ref "CN2") (pin "2") (pinfunction "2_2") (pintype "passive"))
      (node (ref "D6") (pin "C") (pinfunction "C_C") (pintype "passive"))
      (node (ref "D8") (pin "C") (pinfunction "C_C") (pintype "passive"))
      (node (ref "JP10") (pin "2") (pinfunction "2_2") (pintype "passive"))
      (node (ref "JP6") (pin "2") (pinfunction "2_2") (pintype "passive"))
      (node (ref "U8") (pin "3") (pinfunction "VBAT_3") (pintype "power_in"))
      (node (ref "U9") (pin "P$4") (pinfunction "VBAT_P$4") (pintype "power_in"))
      (node (ref "U9") (pin "P$5") (pinfunction "VBAT_P$5") (pintype "power_in"))
      (node (ref "U9") (pin "P$6") (pinfunction "VBAT_P$6") (pintype "power_in"))
    )
    (net (code "94") (name "VBUS") (class "Default")
      (node (ref "U9") (pin "P$25") (pinfunction "VBUS_P$25") (pintype "power_in"))
    )
    (net (code "95") (name "VCCIO") (class "Default")
      (node (ref "IC1") (pin "14") (pinfunction "VCC_14") (pintype "power_in"))
      (node (ref "JP10") (pin "4") (pinfunction "4_4") (pintype "passive"))
    )
    (net (code "96") (name "VRTC") (class "Default")
      (node (ref "C14") (pin "1") (pinfunction "1_1") (pintype "passive"))
      (node (ref "U9") (pin "P$17") (pinfunction "VRTC_P$17") (pintype "power_in"))
    )
    (net (code "97") (name "unconnected-(D7-C5-Pad6)") (class "Default")
      (node (ref "D7") (pin "6") (pinfunction "C5_6") (pintype "passive"))
    )
    (net (code "98") (name "unconnected-(U$25-PadVPP)") (class "Default")
      (node (ref "U$25") (pin "VPP") (pinfunction "VPP_VPP") (pintype "power_in"))
    )
    (net (code "99") (name "unconnected-(U1-NC-Pad1)") (class "Default")
      (node (ref "U1") (pin "1") (pinfunction "NC_1") (pintype "bidirectional"))
    )
    (net (code "100") (name "unconnected-(U1-RSV-Pad8)") (class "Default")
      (node (ref "U1") (pin "8") (pinfunction "RSV_8") (pintype "bidirectional"))
    )
    (net (code "101") (name "unconnected-(U2-PadIOREF)") (class "Default")
      (node (ref "U2") (pin "IOREF") (pinfunction "IOREF_IOREF") (pintype "bidirectional"))
    )
    (net (code "102") (name "unconnected-(U2-PadSCL)") (class "Default")
      (node (ref "U2") (pin "SCL") (pinfunction "SCL_SCL") (pintype "bidirectional"))
    )
    (net (code "103") (name "unconnected-(U2-PadSDA)") (class "Default")
      (node (ref "U2") (pin "SDA") (pinfunction "SDA_SDA") (pintype "bidirectional"))
    )
    (net (code "104") (name "unconnected-(U3-Pad6)") (class "Default")
      (node (ref "U3") (pin "6") (pinfunction "6_6") (pintype "bidirectional"))
    )
    (net (code "105") (name "unconnected-(U4A-CLKOUT-Pad3)") (class "Default")
      (node (ref "U4") (pin "3") (pinfunction "CLKOUT_3") (pintype "output"))
    )
    (net (code "106") (name "unconnected-(U4A-RX0BF-Pad11)") (class "Default")
      (node (ref "U4") (pin "11") (pinfunction "RX0BF_11") (pintype "output"))
    )
    (net (code "107") (name "unconnected-(U4A-RX1BF-Pad10)") (class "Default")
      (node (ref "U4") (pin "10") (pinfunction "RX1BF_10") (pintype "output"))
    )
    (net (code "108") (name "unconnected-(U4A-TX0RTS-Pad4)") (class "Default")
      (node (ref "U4") (pin "4") (pinfunction "TX0RTS_4") (pintype "input"))
    )
    (net (code "109") (name "unconnected-(U4A-TX1RTS-Pad5)") (class "Default")
      (node (ref "U4") (pin "5") (pinfunction "TX1RTS_5") (pintype "input"))
    )
    (net (code "110") (name "unconnected-(U4A-TX2RTS-Pad6)") (class "Default")
      (node (ref "U4") (pin "6") (pinfunction "TX2RTS_6") (pintype "input"))
    )
    (net (code "111") (name "unconnected-(U5-VREF-Pad5)") (class "Default")
      (node (ref "U5") (pin "5") (pinfunction "VREF_5") (pintype "bidirectional"))
    )
    (net (code "112") (name "unconnected-(U6-4A-Pad9)") (class "Default")
      (node (ref "U6") (pin "9") (pinfunction "4A_9") (pintype "bidirectional"))
    )
    (net (code "113") (name "unconnected-(U6-4Y-Pad10)") (class "Default")
      (node (ref "U6") (pin "10") (pinfunction "4Y_10") (pintype "bidirectional"))
    )
    (net (code "114") (name "unconnected-(U6-5A-Pad11)") (class "Default")
      (node (ref "U6") (pin "11") (pinfunction "5A_11") (pintype "bidirectional"))
    )
    (net (code "115") (name "unconnected-(U6-5Y-Pad12)") (class "Default")
      (node (ref "U6") (pin "12") (pinfunction "5Y_12") (pintype "bidirectional"))
    )
    (net (code "116") (name "unconnected-(U6-6A-Pad14)") (class "Default")
      (node (ref "U6") (pin "14") (pinfunction "6A_14") (pintype "bidirectional"))
    )
    (net (code "117") (name "unconnected-(U6-6Y-Pad15)") (class "Default")
      (node (ref "U6") (pin "15") (pinfunction "6Y_15") (pintype "bidirectional"))
    )
    (net (code "118") (name "unconnected-(U9-1PPS-PadP$37)") (class "Default")
      (node (ref "U9") (pin "P$37") (pinfunction "1PPS_P$37") (pintype "input"))
    )
    (net (code "119") (name "unconnected-(U9-ADC2-PadP$24)") (class "Default")
      (node (ref "U9") (pin "P$24") (pinfunction "ADC2_P$24") (pintype "input"))
    )
    (net (code "120") (name "unconnected-(U9-ANT_BT-PadP$53)") (class "Default")
      (node (ref "U9") (pin "P$53") (pinfunction "ANT_BT_P$53") (pintype "bidirectional"))
    )
    (net (code "121") (name "unconnected-(U9-COL0-PadP$62)") (class "Default")
      (node (ref "U9") (pin "P$62") (pinfunction "COL0_P$62") (pintype "input"))
    )
    (net (code "122") (name "unconnected-(U9-COL1-PadP$61)") (class "Default")
      (node (ref "U9") (pin "P$61") (pinfunction "COL1_P$61") (pintype "input"))
    )
    (net (code "123") (name "unconnected-(U9-COL2-PadP$60)") (class "Default")
      (node (ref "U9") (pin "P$60") (pinfunction "COL2_P$60") (pintype "input"))
    )
    (net (code "124") (name "unconnected-(U9-COL3-PadP$59)") (class "Default")
      (node (ref "U9") (pin "P$59") (pinfunction "COL3_P$59") (pintype "input"))
    )
    (net (code "125") (name "unconnected-(U9-CTS-PadP$12)") (class "Default")
      (node (ref "U9") (pin "P$12") (pinfunction "CTS_P$12") (pintype "output"))
    )
    (net (code "126") (name "unconnected-(U9-DCD-PadP$11)") (class "Default")
      (node (ref "U9") (pin "P$11") (pinfunction "DCD_P$11") (pintype "output"))
    )
    (net (code "127") (name "unconnected-(U9-DTR-PadP$9)") (class "Default")
      (node (ref "U9") (pin "P$9") (pinfunction "DTR_P$9") (pintype "input"))
    )
    (net (code "128") (name "unconnected-(U9-GPIO5-PadP$43)") (class "Default")
      (node (ref "U9") (pin "P$43") (pinfunction "GPIO5_P$43") (pintype "bidirectional"))
    )
    (net (code "129") (name "unconnected-(U9-GPIO6-PadP$44)") (class "Default")
      (node (ref "U9") (pin "P$44") (pinfunction "GPIO6_P$44") (pintype "bidirectional"))
    )
    (net (code "130") (name "unconnected-(U9-PCM_CLK-PadP$46)") (class "Default")
      (node (ref "U9") (pin "P$46") (pinfunction "PCM_CLK_P$46") (pintype "input"))
    )
    (net (code "131") (name "unconnected-(U9-PCM_IN-PadP$47)") (class "Default")
      (node (ref "U9") (pin "P$47") (pinfunction "PCM_IN_P$47") (pintype "input"))
    )
    (net (code "132") (name "unconnected-(U9-PCM_OUT-PadP$48)") (class "Default")
      (node (ref "U9") (pin "P$48") (pinfunction "PCM_OUT_P$48") (pintype "output"))
    )
    (net (code "133") (name "unconnected-(U9-PCM_SYNC-PadP$45)") (class "Default")
      (node (ref "U9") (pin "P$45") (pinfunction "PCM_SYNC_P$45") (pintype "output"))
    )
    (net (code "134") (name "unconnected-(U9-PWM2-PadP$41)") (class "Default")
      (node (ref "U9") (pin "P$41") (pinfunction "PWM2_P$41") (pintype "output"))
    )
    (net (code "135") (name "unconnected-(U9-RF_SYNC-PadP$63)") (class "Default")
      (node (ref "U9") (pin "P$63") (pinfunction "RF_SYNC_P$63") (pintype "output"))
    )
    (net (code "136") (name "unconnected-(U9-ROW0-PadP$58)") (class "Default")
      (node (ref "U9") (pin "P$58") (pinfunction "ROW0_P$58") (pintype "output"))
    )
    (net (code "137") (name "unconnected-(U9-ROW1-PadP$57)") (class "Default")
      (node (ref "U9") (pin "P$57") (pinfunction "ROW1_P$57") (pintype "output"))
    )
    (net (code "138") (name "unconnected-(U9-ROW2-PadP$56)") (class "Default")
      (node (ref "U9") (pin "P$56") (pinfunction "ROW2_P$56") (pintype "output"))
    )
    (net (code "139") (name "unconnected-(U9-ROW3-PadP$55)") (class "Default")
      (node (ref "U9") (pin "P$55") (pinfunction "ROW3_P$55") (pintype "output"))
    )
    (net (code "140") (name "unconnected-(U9-SCL-PadP$39)") (class "Default")
      (node (ref "U9") (pin "P$39") (pinfunction "SCL_P$39") (pintype "output"))
    )
    (net (code "141") (name "unconnected-(U9-SDA-PadP$38)") (class "Default")
      (node (ref "U9") (pin "P$38") (pinfunction "SDA_P$38") (pintype "bidirectional"))
    )
    (net (code "142") (name "unconnected-(U9-SIM_PRE-PadP$33)") (class "Default")
      (node (ref "U9") (pin "P$33") (pinfunction "SIM_PRE_P$33") (pintype "input"))
    )
    (net (code "143") (name "unconnected-(U9-USB_DM-PadP$27)") (class "Default")
      (node (ref "U9") (pin "P$27") (pinfunction "USB_DM_P$27") (pintype "bidirectional"))
    )
    (net (code "144") (name "unconnected-(U9-USB_DP-PadP$26)") (class "Default")
      (node (ref "U9") (pin "P$26") (pinfunction "USB_DP_P$26") (pintype "bidirectional"))
    )
    (net (code "145") (name "unconnected-(X2-PadD+)") (class "Default")
      (node (ref "X2") (pin "D+") (pinfunction "D+_D+") (pintype "bidirectional"))
    )
    (net (code "146") (name "unconnected-(X2-PadD-)") (class "Default")
      (node (ref "X2") (pin "D-") (pinfunction "D-_D-") (pintype "bidirectional"))
    )
    (net (code "147") (name "unconnected-(X2-PadID)") (class "Default")
      (node (ref "X2") (pin "ID") (pinfunction "ID_ID") (pintype "bidirectional"))
    )
  )
)
